# WNG_1_0.net
KiCad netlist of a schematic drawn in EAGLE
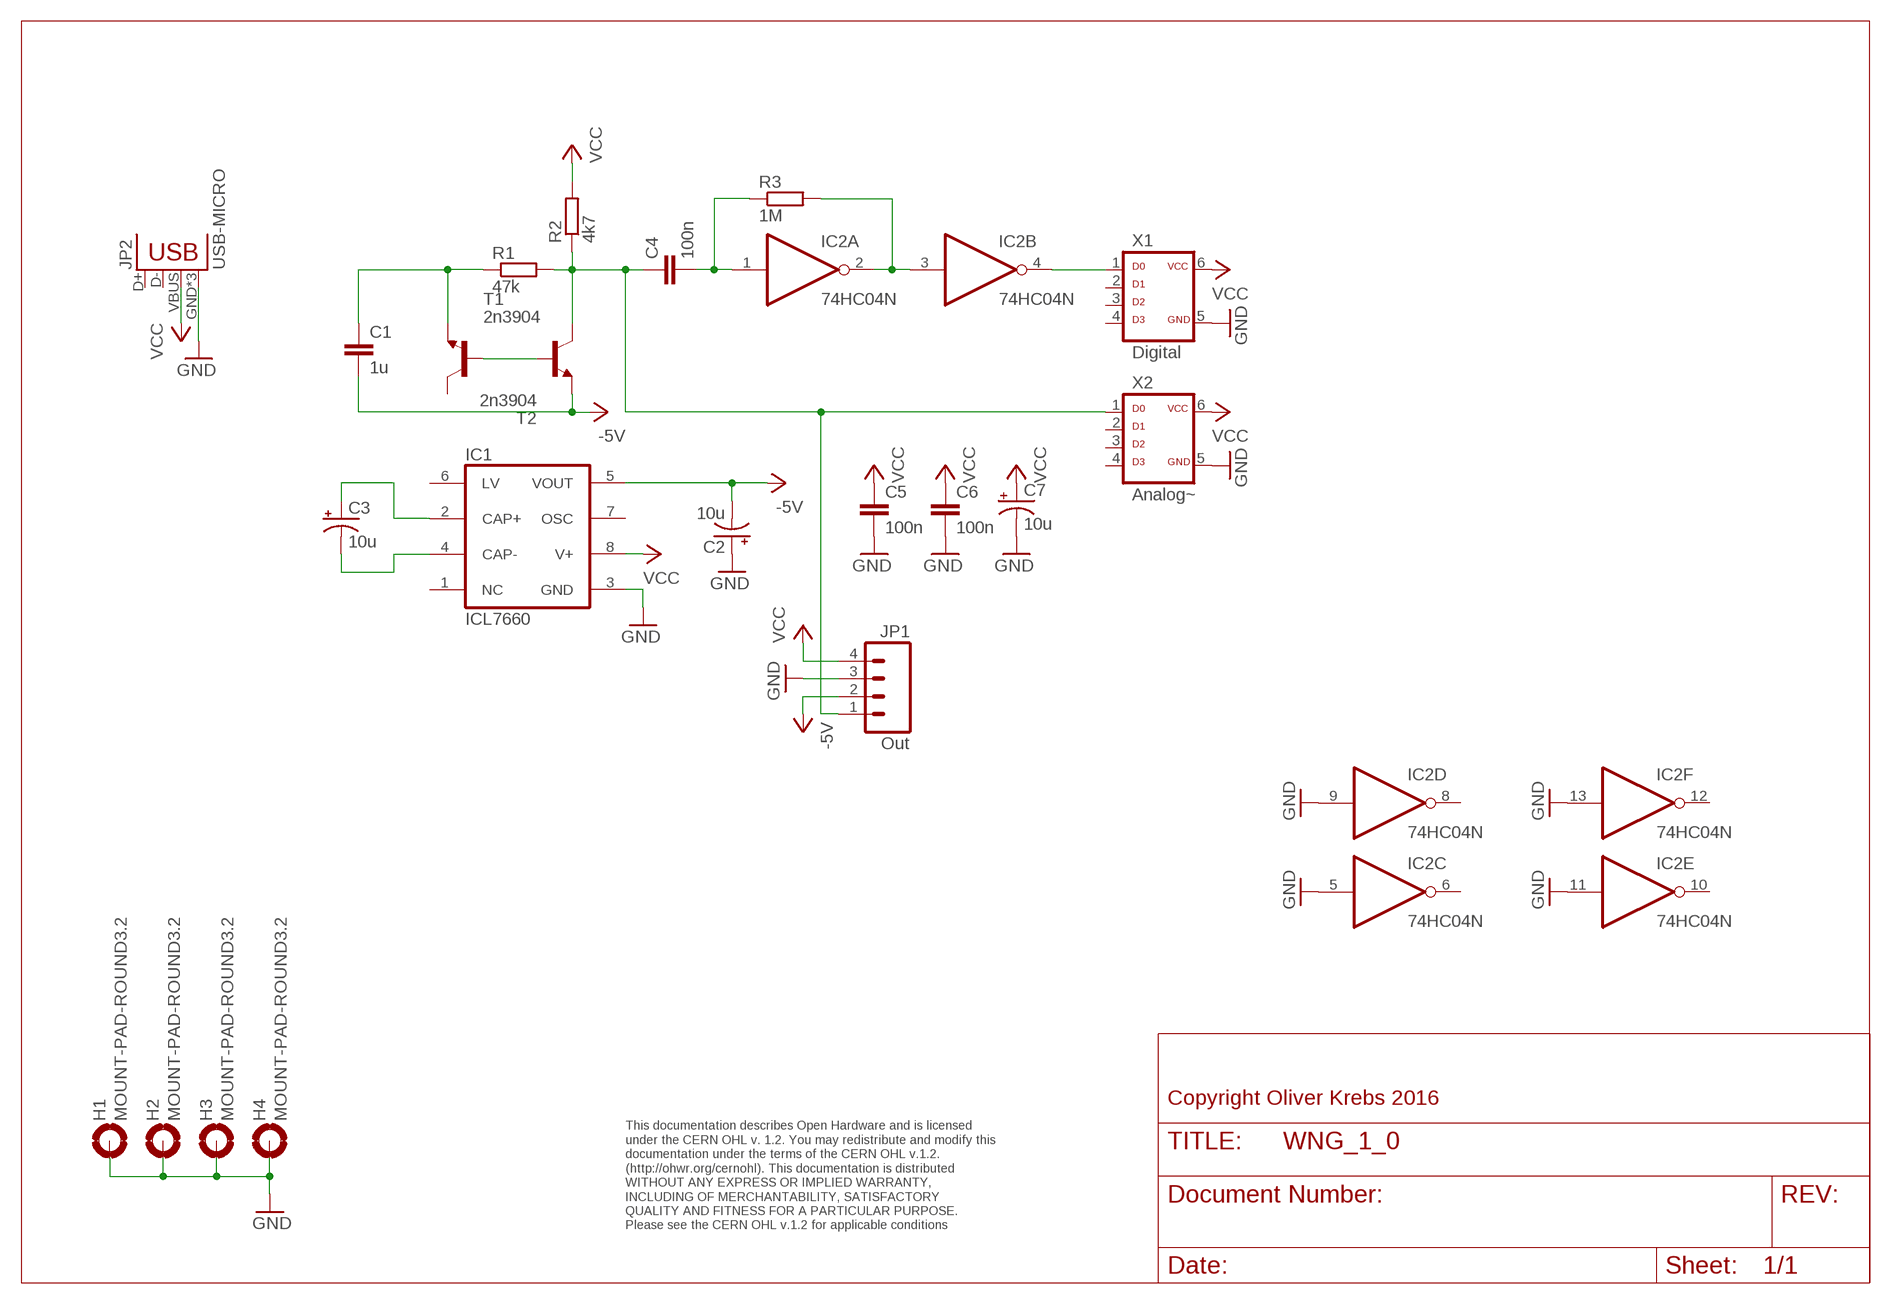
[diagram p0: schematic, sheet 1]

(export (version "E")
  (design (tool "Eeschema 10.0.6"))
  (components
    (comp (ref "C1")
      (value "1u")
      (footprint "eagle-import:CAP-PTH-5MM")
      (libsource (lib "eagle-import") (part "CAPPTH1"))
    )
    (comp (ref "C2")
      (value "10u")
      (footprint "eagle-import:CPOL-RADIAL-10UF-25V")
      (libsource (lib "eagle-import") (part "CAP_POLPTH2"))
    )
    (comp (ref "C3")
      (value "10u")
      (footprint "eagle-import:CPOL-RADIAL-10UF-25V")
      (libsource (lib "eagle-import") (part "CAP_POLPTH2"))
    )
    (comp (ref "C4")
      (value "100n")
      (footprint "eagle-import:CAP-PTH-5MM")
      (libsource (lib "eagle-import") (part "CAPPTH1"))
    )
    (comp (ref "C5")
      (value "100n")
      (footprint "eagle-import:CAP-PTH-5MM")
      (libsource (lib "eagle-import") (part "CAPPTH1"))
    )
    (comp (ref "C6")
      (value "100n")
      (footprint "eagle-import:CAP-PTH-5MM")
      (libsource (lib "eagle-import") (part "CAPPTH1"))
    )
    (comp (ref "C7")
      (value "10u")
      (footprint "eagle-import:CPOL-RADIAL-10UF-25V")
      (libsource (lib "eagle-import") (part "CAP_POLPTH2"))
    )
    (comp (ref "H1")
      (value "MOUNT-PAD-ROUND3.2")
      (footprint "eagle-import:3,2-PAD")
      (libsource (lib "eagle-import") (part "MOUNT-PAD-ROUND3.2"))
    )
    (comp (ref "H2")
      (value "MOUNT-PAD-ROUND3.2")
      (footprint "eagle-import:3,2-PAD")
      (libsource (lib "eagle-import") (part "MOUNT-PAD-ROUND3.2"))
    )
    (comp (ref "H3")
      (value "MOUNT-PAD-ROUND3.2")
      (footprint "eagle-import:3,2-PAD")
      (libsource (lib "eagle-import") (part "MOUNT-PAD-ROUND3.2"))
    )
    (comp (ref "H4")
      (value "MOUNT-PAD-ROUND3.2")
      (footprint "eagle-import:3,2-PAD")
      (libsource (lib "eagle-import") (part "MOUNT-PAD-ROUND3.2"))
    )
    (comp (ref "IC1")
      (value "ICL7660")
      (footprint "eagle-import:DIL08")
      (fields (field (name "MF") "INTERSIL") (field (name "MPN") "ICL7660CPA"))
      (libsource (lib "eagle-import") (part "ICL7660CPA"))
    )
    (comp (ref "IC2")
      (value "74HC04N")
      (footprint "eagle-import:DIL14")
      (libsource (lib "eagle-import") (part "7404NHC"))
    )
    (comp (ref "JP1")
      (value "Out")
      (footprint "eagle-import:1X04")
      (libsource (lib "eagle-import") (part "M04PTH"))
    )
    (comp (ref "JP2")
      (value "USB-MICRO")
      (footprint "eagle-import:USB-MICROB2")
      (libsource (lib "eagle-import") (part "USB-MICROB2"))
    )
    (comp (ref "R1")
      (value "47k")
      (footprint "eagle-import:0207_10")
      (libsource (lib "eagle-import") (part "R-EU_0207/10"))
    )
    (comp (ref "R2")
      (value "4k7")
      (footprint "eagle-import:0207_10")
      (libsource (lib "eagle-import") (part "R-EU_0207/10"))
    )
    (comp (ref "R3")
      (value "1M")
      (footprint "eagle-import:0207_10")
      (libsource (lib "eagle-import") (part "R-EU_0207/10"))
    )
    (comp (ref "T1")
      (value "2n3904")
      (footprint "eagle-import:TO92-EBC")
      (libsource (lib "eagle-import") (part "-NPN-TO92-EBC2N3904"))
    )
    (comp (ref "T2")
      (value "2n3904")
      (footprint "eagle-import:TO92-EBC")
      (libsource (lib "eagle-import") (part "-NPN-TO92-EBC2N3904"))
    )
    (comp (ref "X1")
      (value "Digital")
      (footprint "eagle-import:ML-6")
      (libsource (lib "eagle-import") (part "ML6D"))
    )
    (comp (ref "X2")
      (value "Analog~")
      (footprint "eagle-import:ML-6")
      (libsource (lib "eagle-import") (part "ML6D"))
    )
  )
  (nets
    (net (code "1") (name "-5V") (class "Default")
      (node (ref "C1") (pin "2") (pinfunction "2_2") (pintype "passive"))
      (node (ref "C2") (pin "2") (pinfunction "-_2") (pintype "passive"))
      (node (ref "IC1") (pin "5") (pinfunction "VOUT_5") (pintype "output"))
      (node (ref "JP1") (pin "2") (pinfunction "2_2") (pintype "passive"))
      (node (ref "T1") (pin "E") (pinfunction "E_E") (pintype "passive"))
    )
    (net (code "2") (name "GND") (class "Default")
      (node (ref "C2") (pin "1") (pinfunction "+_1") (pintype "passive"))
      (node (ref "C5") (pin "2") (pinfunction "2_2") (pintype "passive"))
      (node (ref "C6") (pin "2") (pinfunction "2_2") (pintype "passive"))
      (node (ref "C7") (pin "2") (pinfunction "-_2") (pintype "passive"))
      (node (ref "H1") (pin "B3,2") (pinfunction "MOUNT_B3,2") (pintype "passive"))
      (node (ref "H2") (pin "B3,2") (pinfunction "MOUNT_B3,2") (pintype "passive"))
      (node (ref "H3") (pin "B3,2") (pinfunction "MOUNT_B3,2") (pintype "passive"))
      (node (ref "H4") (pin "B3,2") (pinfunction "MOUNT_B3,2") (pintype "passive"))
      (node (ref "IC1") (pin "3") (pinfunction "GND_3") (pintype "power_in"))
      (node (ref "IC2") (pin "11") (pinfunction "I_11") (pintype "input"))
      (node (ref "IC2") (pin "13") (pinfunction "I_13") (pintype "input"))
      (node (ref "IC2") (pin "5") (pinfunction "I_5") (pintype "input"))
      (node (ref "IC2") (pin "9") (pinfunction "I_9") (pintype "input"))
      (node (ref "JP1") (pin "3") (pinfunction "3_3") (pintype "passive"))
      (node (ref "JP2") (pin "GND") (pinfunction "GND_GND") (pintype "bidirectional"))
      (node (ref "JP2") (pin "MT1") (pinfunction "GND_MT1") (pintype "bidirectional"))
      (node (ref "JP2") (pin "MT2") (pinfunction "GND_MT2") (pintype "bidirectional"))
      (node (ref "X1") (pin "5") (pinfunction "5_5") (pintype "passive"))
      (node (ref "X2") (pin "5") (pinfunction "5_5") (pintype "passive"))
    )
    (net (code "3") (name "Net-(C1-Pad1)") (class "Default")
      (node (ref "C1") (pin "1") (pinfunction "1_1") (pintype "passive"))
      (node (ref "R1") (pin "1") (pinfunction "1_1") (pintype "passive"))
      (node (ref "T2") (pin "E") (pinfunction "E_E") (pintype "passive"))
    )
    (net (code "4") (name "Net-(C3-+)") (class "Default")
      (node (ref "C3") (pin "1") (pinfunction "+_1") (pintype "passive"))
      (node (ref "IC1") (pin "2") (pinfunction "CAP+_2") (pintype "passive"))
    )
    (net (code "5") (name "Net-(C3--)") (class "Default")
      (node (ref "C3") (pin "2") (pinfunction "-_2") (pintype "passive"))
      (node (ref "IC1") (pin "4") (pinfunction "CAP-_4") (pintype "passive"))
    )
    (net (code "6") (name "Net-(C4-Pad1)") (class "Default")
      (node (ref "C4") (pin "1") (pinfunction "1_1") (pintype "passive"))
      (node (ref "JP1") (pin "1") (pinfunction "1_1") (pintype "passive"))
      (node (ref "R1") (pin "2") (pinfunction "2_2") (pintype "passive"))
      (node (ref "R2") (pin "1") (pinfunction "1_1") (pintype "passive"))
      (node (ref "T1") (pin "C") (pinfunction "C_C") (pintype "passive"))
      (node (ref "X2") (pin "1") (pinfunction "1_1") (pintype "passive"))
    )
    (net (code "7") (name "Net-(IC2A-I)") (class "Default")
      (node (ref "C4") (pin "2") (pinfunction "2_2") (pintype "passive"))
      (node (ref "IC2") (pin "1") (pinfunction "I_1") (pintype "input"))
      (node (ref "R3") (pin "1") (pinfunction "1_1") (pintype "passive"))
    )
    (net (code "8") (name "Net-(IC2A-O)") (class "Default")
      (node (ref "IC2") (pin "2") (pinfunction "O_2") (pintype "output"))
      (node (ref "IC2") (pin "3") (pinfunction "I_3") (pintype "input"))
      (node (ref "R3") (pin "2") (pinfunction "2_2") (pintype "passive"))
    )
    (net (code "9") (name "Net-(IC2B-O)") (class "Default")
      (node (ref "IC2") (pin "4") (pinfunction "O_4") (pintype "output"))
      (node (ref "X1") (pin "1") (pinfunction "1_1") (pintype "passive"))
    )
    (net (code "10") (name "Net-(T1-PadB)") (class "Default")
      (node (ref "T1") (pin "B") (pinfunction "B_B") (pintype "passive"))
      (node (ref "T2") (pin "B") (pinfunction "B_B") (pintype "passive"))
    )
    (net (code "11") (name "VCC") (class "Default")
      (node (ref "C5") (pin "1") (pinfunction "1_1") (pintype "passive"))
      (node (ref "C6") (pin "1") (pinfunction "1_1") (pintype "passive"))
      (node (ref "C7") (pin "1") (pinfunction "+_1") (pintype "passive"))
      (node (ref "IC1") (pin "8") (pinfunction "V+_8") (pintype "power_in"))
      (node (ref "JP1") (pin "4") (pinfunction "4_4") (pintype "passive"))
      (node (ref "JP2") (pin "VBUS") (pinfunction "VBUS_VBUS") (pintype "bidirectional"))
      (node (ref "R2") (pin "2") (pinfunction "2_2") (pintype "passive"))
      (node (ref "X1") (pin "6") (pinfunction "6_6") (pintype "passive"))
      (node (ref "X2") (pin "6") (pinfunction "6_6") (pintype "passive"))
    )
    (net (code "12") (name "unconnected-(IC1-LV-Pad6)") (class "Default")
      (node (ref "IC1") (pin "6") (pinfunction "LV_6") (pintype "passive"))
    )
    (net (code "13") (name "unconnected-(IC1-NC-Pad1)") (class "Default")
      (node (ref "IC1") (pin "1") (pinfunction "NC_1") (pintype "no_connect"))
    )
    (net (code "14") (name "unconnected-(IC1-OSC-Pad7)") (class "Default")
      (node (ref "IC1") (pin "7") (pinfunction "OSC_7") (pintype "output"))
    )
    (net (code "15") (name "unconnected-(IC2C-O-Pad6)") (class "Default")
      (node (ref "IC2") (pin "6") (pinfunction "O_6") (pintype "output"))
    )
    (net (code "16") (name "unconnected-(IC2D-O-Pad8)") (class "Default")
      (node (ref "IC2") (pin "8") (pinfunction "O_8") (pintype "output"))
    )
    (net (code "17") (name "unconnected-(IC2E-O-Pad10)") (class "Default")
      (node (ref "IC2") (pin "10") (pinfunction "O_10") (pintype "output"))
    )
    (net (code "18") (name "unconnected-(IC2F-O-Pad12)") (class "Default")
      (node (ref "IC2") (pin "12") (pinfunction "O_12") (pintype "output"))
    )
    (net (code "19") (name "unconnected-(JP2-PadD+)") (class "Default")
      (node (ref "JP2") (pin "D+") (pinfunction "D+_D+") (pintype "bidirectional"))
    )
    (net (code "20") (name "unconnected-(JP2-PadD-)") (class "Default")
      (node (ref "JP2") (pin "D-") (pinfunction "D-_D-") (pintype "bidirectional"))
    )
    (net (code "21") (name "unconnected-(T2-PadC)") (class "Default")
      (node (ref "T2") (pin "C") (pinfunction "C_C") (pintype "passive"))
    )
    (net (code "22") (name "unconnected-(X1-Pad2)") (class "Default")
      (node (ref "X1") (pin "2") (pinfunction "2_2") (pintype "passive"))
    )
    (net (code "23") (name "unconnected-(X1-Pad3)") (class "Default")
      (node (ref "X1") (pin "3") (pinfunction "3_3") (pintype "passive"))
    )
    (net (code "24") (name "unconnected-(X1-Pad4)") (class "Default")
      (node (ref "X1") (pin "4") (pinfunction "4_4") (pintype "passive"))
    )
    (net (code "25") (name "unconnected-(X2-Pad2)") (class "Default")
      (node (ref "X2") (pin "2") (pinfunction "2_2") (pintype "passive"))
    )
    (net (code "26") (name "unconnected-(X2-Pad3)") (class "Default")
      (node (ref "X2") (pin "3") (pinfunction "3_3") (pintype "passive"))
    )
    (net (code "27") (name "unconnected-(X2-Pad4)") (class "Default")
      (node (ref "X2") (pin "4") (pinfunction "4_4") (pintype "passive"))
    )
  )
)
